# 3_LEDDRIVERS.net
KiCad netlist of a schematic drawn in Altium Designer
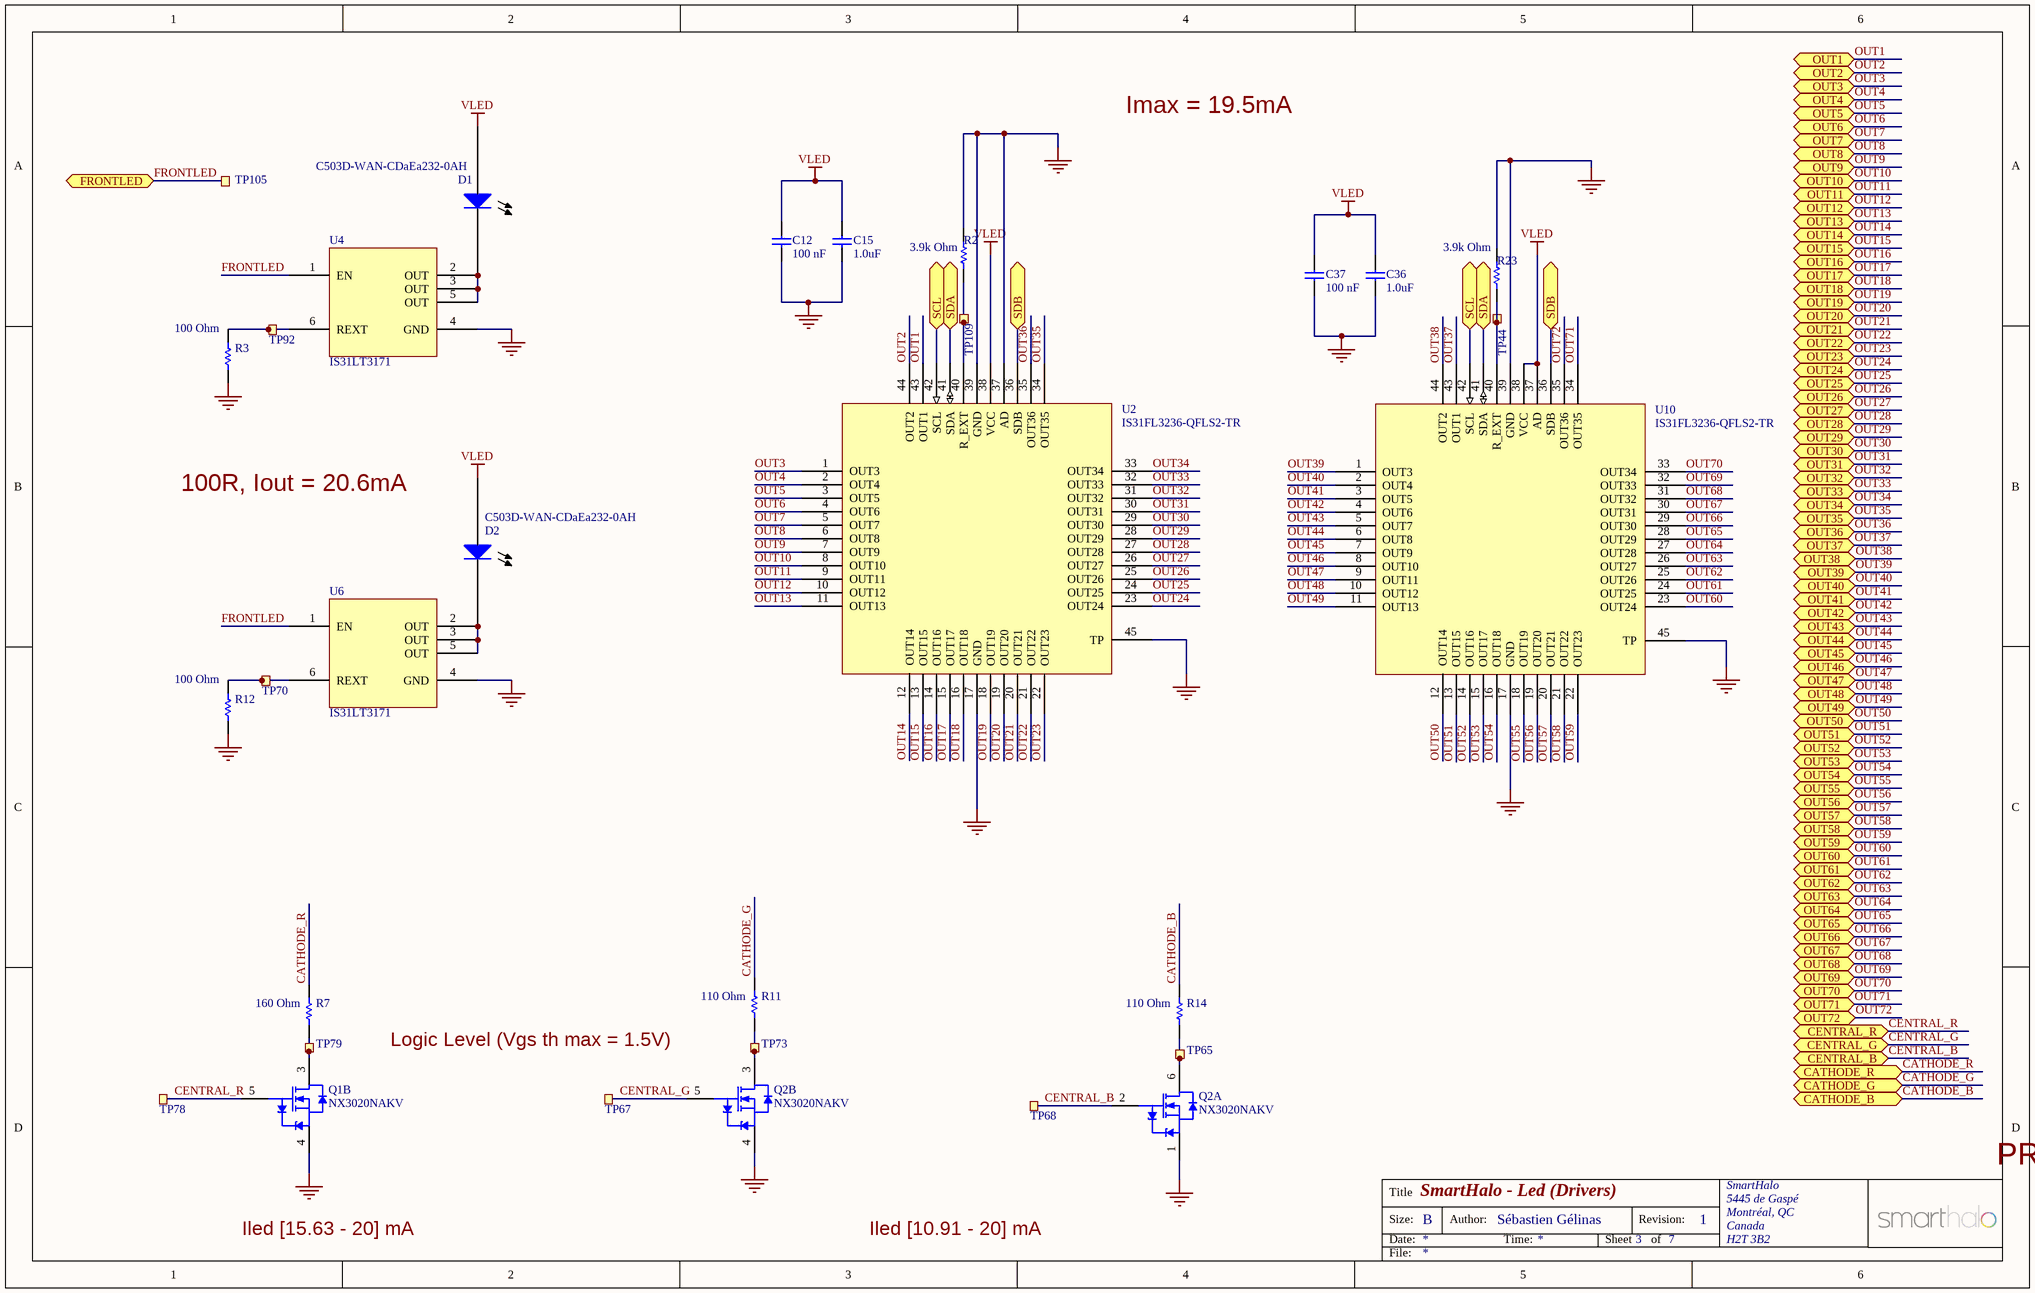
[diagram p0: 3_LEDDRIVERS.SchDoc]

(export (version "E")
  (design (tool "Eeschema 10.0.6"))
  (components
    (comp (ref "C12")
      (value "100 nF")
      (footprint "Varitron_CAP0402")
      (description "100 nF 10V X7R 10% 0402 (1005 Metric)  SMD")
      (fields (field (name "TOLERANCE") "10%"))
      (libsource (lib "SmartHalo") (part "Varitron_CAP0402"))
    )
    (comp (ref "C15")
      (value "1.0uF")
      (footprint "Varitron_CAP0603")
      (description "1uF 10V X7R 10% 0603 (1608 Metric)  SMD")
      (fields (field (name "TOLERANCE") "10%"))
      (libsource (lib "SmartHalo") (part "Varitron_CAP0603"))
    )
    (comp (ref "C36")
      (value "1.0uF")
      (footprint "Varitron_CAP0603")
      (description "1uF 10V X7R 10% 0603 (1608 Metric)  SMD")
      (fields (field (name "TOLERANCE") "10%"))
      (libsource (lib "SmartHalo") (part "Varitron_CAP0603"))
    )
    (comp (ref "C37")
      (value "100 nF")
      (footprint "Varitron_CAP0402")
      (description "100 nF 10V X7R 10% 0402 (1005 Metric)  SMD")
      (fields (field (name "TOLERANCE") "10%"))
      (libsource (lib "SmartHalo") (part "Varitron_CAP0402"))
    )
    (comp (ref "D1")
      (value "C503D-WAN-CDaEa232-0AH")
      (footprint "FRONTLED_PADS")
      (description "Cree 5mm Round LED C503D-WAN-CDaEa232-0AH")
      (fields (field (name "MANUFACTURER") "Cree"))
      (libsource (lib "SmartHalo") (part "C503D-WAN-CDaEa232-0AH"))
    )
    (comp (ref "D2")
      (value "C503D-WAN-CDaEa232-0AH")
      (footprint "FRONTLED_PADS")
      (description "Cree 5mm Round LED C503D-WAN-CDaEa232-0AH")
      (fields (field (name "MANUFACTURER") "Cree"))
      (libsource (lib "SmartHalo") (part "C503D-WAN-CDaEa232-0AH"))
    )
    (comp (ref "Q1")
      (value "NX3020NAKV")
      (footprint "SOT666")
      (description "30 V, 200 mA dual N-channel Trench MOSFET")
      (fields (field (name "MANUFACTURER") "NXP Semiconductors"))
      (libsource (lib "SmartHalo") (part "NX3020NAKV"))
    )
    (comp (ref "Q2")
      (value "NX3020NAKV")
      (footprint "SOT666")
      (description "30 V, 200 mA dual N-channel Trench MOSFET")
      (fields (field (name "MANUFACTURER") "NXP Semiconductors"))
      (libsource (lib "SmartHalo") (part "NX3020NAKV"))
    )
    (comp (ref "R2")
      (value "3.9k Ohm")
      (footprint "Varitron_RES0402")
      (description "3K9 0.063W 5%  0402 (1005 Metric)  SMD")
      (fields (field (name "TOLERANCE") "5%") (field (name "POWER") "0.063W"))
      (libsource (lib "SmartHalo") (part "Varitron_RES0402"))
    )
    (comp (ref "R3")
      (value "100 Ohm")
      (footprint "Varitron_RES0402")
      (description "100R 0.1W 5% 0402 (1005 Metric)  SMD")
      (fields (field (name "TOLERANCE") "5%") (field (name "POWER") "0.1W"))
      (libsource (lib "SmartHalo") (part "Varitron_RES0402"))
    )
    (comp (ref "R7")
      (value "160 Ohm")
      (footprint "Varitron_RES0402")
      (description "160R 0.1W 5% 0402 (1005 Metric)  SMD")
      (fields (field (name "TOLERANCE") "5%") (field (name "POWER") "0.1W"))
      (libsource (lib "SmartHalo") (part "Varitron_RES0402"))
    )
    (comp (ref "R11")
      (value "110 Ohm")
      (footprint "Varitron_RES0402")
      (description "110R 0.1W 5% 0402 (1005 Metric)  SMD")
      (fields (field (name "TOLERANCE") "5%") (field (name "POWER") "0.1W"))
      (libsource (lib "SmartHalo") (part "Varitron_RES0402"))
    )
    (comp (ref "R12")
      (value "100 Ohm")
      (footprint "Varitron_RES0402")
      (description "100R 0.1W 5% 0402 (1005 Metric)  SMD")
      (fields (field (name "TOLERANCE") "5%") (field (name "POWER") "0.1W"))
      (libsource (lib "SmartHalo") (part "Varitron_RES0402"))
    )
    (comp (ref "R14")
      (value "110 Ohm")
      (footprint "Varitron_RES0402")
      (description "110R 0.1W 5% 0402 (1005 Metric)  SMD")
      (fields (field (name "TOLERANCE") "5%") (field (name "POWER") "0.1W"))
      (libsource (lib "SmartHalo") (part "Varitron_RES0402"))
    )
    (comp (ref "R23")
      (value "3.9k Ohm")
      (footprint "Varitron_RES0402")
      (description "3K9 0.063W 5%  0402 (1005 Metric)  SMD")
      (fields (field (name "TOLERANCE") "5%") (field (name "POWER") "0.063W"))
      (libsource (lib "SmartHalo") (part "Varitron_RES0402"))
    )
    (comp (ref "TP44")
      (value "~")
      (footprint "TESTPAD-TH-35mils")
      (description "Testpoint, through hole, 35 mils")
      (libsource (lib "SmartHalo") (part "TESTPAD_TH_35mils"))
    )
    (comp (ref "TP65")
      (value "~")
      (footprint "TESTPAD-TH-35mils")
      (description "Testpoint, through hole, 35 mils")
      (libsource (lib "SmartHalo") (part "TESTPAD_TH_35mils"))
    )
    (comp (ref "TP67")
      (value "~")
      (footprint "TESTPAD-TH-35mils")
      (description "Testpoint, through hole, 35 mils")
      (libsource (lib "") (part "TESTPAD_TH_35mils_1"))
    )
    (comp (ref "TP68")
      (value "~")
      (footprint "TESTPAD-TH-35mils")
      (description "Testpoint, through hole, 35 mils")
      (libsource (lib "") (part "TESTPAD_TH_35mils_1"))
    )
    (comp (ref "TP70")
      (value "~")
      (footprint "TESTPAD-TH-35mils")
      (description "Testpoint, through hole, 35 mils")
      (libsource (lib "") (part "TESTPAD_TH_35mils_2"))
    )
    (comp (ref "TP73")
      (value "~")
      (footprint "TESTPAD-TH-35mils")
      (description "Testpoint, through hole, 35 mils")
      (libsource (lib "SmartHalo") (part "TESTPAD_TH_35mils"))
    )
    (comp (ref "TP78")
      (value "~")
      (footprint "TESTPAD-TH-35mils")
      (description "Testpoint, through hole, 35 mils")
      (libsource (lib "") (part "TESTPAD_TH_35mils_1"))
    )
    (comp (ref "TP79")
      (value "~")
      (footprint "TESTPAD-TH-35mils")
      (description "Testpoint, through hole, 35 mils")
      (libsource (lib "SmartHalo") (part "TESTPAD_TH_35mils"))
    )
    (comp (ref "TP92")
      (value "~")
      (footprint "TESTPAD-TH-35mils")
      (description "Testpoint, through hole, 35 mils")
      (libsource (lib "") (part "TESTPAD_TH_35mils_2"))
    )
    (comp (ref "TP105")
      (value "~")
      (footprint "TESTPAD-TH-35mils")
      (description "Testpoint, through hole, 35 mils")
      (libsource (lib "") (part "TESTPAD_TH_35mils_2"))
    )
    (comp (ref "TP109")
      (value "~")
      (footprint "TESTPAD-TH-35mils")
      (description "Testpoint, through hole, 35 mils")
      (libsource (lib "SmartHalo") (part "TESTPAD_TH_35mils"))
    )
    (comp (ref "U2")
      (value "IS31FL3236-QFLS2-TR")
      (footprint "QFN-44")
      (description "IC 36 CHANNELS LED DRIVER")
      (fields (field (name "MANUFACTURER") "ISSI"))
      (libsource (lib "SmartHalo_Symbols") (part "IS31FL3236-QFLS2-TR"))
    )
    (comp (ref "U4")
      (value "IS31LT3171")
      (footprint "SOT23-6")
      (description "10-TO-150MA CONSTANT-CURRENT LED DRIVER")
      (fields (field (name "MANUFACTURER") "ISSI"))
      (libsource (lib "SmartHalo") (part "IS31LT3171"))
    )
    (comp (ref "U6")
      (value "IS31LT3171")
      (footprint "SOT23-6")
      (description "10-TO-150MA CONSTANT-CURRENT LED DRIVER")
      (fields (field (name "MANUFACTURER") "ISSI"))
      (libsource (lib "SmartHalo") (part "IS31LT3171"))
    )
    (comp (ref "U10")
      (value "IS31FL3236-QFLS2-TR")
      (footprint "QFN-44")
      (description "IC 36 CHANNELS LED DRIVER")
      (fields (field (name "MANUFACTURER") "ISSI"))
      (libsource (lib "SmartHalo_Symbols") (part "IS31FL3236-QFLS2-TR"))
    )
  )
  (nets
    (net (code "1") (name "/CATHODE_B") (class "Default")
      (node (ref "R14") (pin "2") (pinfunction "2_2") (pintype "passive"))
    )
    (net (code "2") (name "/CATHODE_G") (class "Default")
      (node (ref "R11") (pin "2") (pinfunction "2_2") (pintype "passive"))
    )
    (net (code "3") (name "/CATHODE_R") (class "Default")
      (node (ref "R7") (pin "2") (pinfunction "2_2") (pintype "passive"))
    )
    (net (code "4") (name "/CENTRAL_B") (class "Default")
      (node (ref "Q2") (pin "2") (pinfunction "G1_2") (pintype "passive"))
      (node (ref "TP68") (pin "1") (pinfunction "1_1") (pintype "passive"))
    )
    (net (code "5") (name "/CENTRAL_G") (class "Default")
      (node (ref "Q2") (pin "5") (pinfunction "G2_5") (pintype "passive"))
      (node (ref "TP67") (pin "1") (pinfunction "1_1") (pintype "passive"))
    )
    (net (code "6") (name "/CENTRAL_R") (class "Default")
      (node (ref "Q1") (pin "5") (pinfunction "G2_5") (pintype "passive"))
      (node (ref "TP78") (pin "1") (pinfunction "1_1") (pintype "passive"))
    )
    (net (code "7") (name "/FRONTLED") (class "Default")
      (node (ref "TP105") (pin "1") (pinfunction "1_1") (pintype "passive"))
      (node (ref "U4") (pin "1") (pinfunction "EN_1") (pintype "passive"))
      (node (ref "U6") (pin "1") (pinfunction "EN_1") (pintype "passive"))
    )
    (net (code "8") (name "/OUT1") (class "Default")
      (node (ref "U2") (pin "43") (pinfunction "OUT1_43") (pintype "passive"))
    )
    (net (code "9") (name "/OUT2") (class "Default")
      (node (ref "U2") (pin "44") (pinfunction "OUT2_44") (pintype "passive"))
    )
    (net (code "10") (name "/OUT3") (class "Default")
      (node (ref "U2") (pin "1") (pinfunction "OUT3_1") (pintype "passive"))
    )
    (net (code "11") (name "/OUT4") (class "Default")
      (node (ref "U2") (pin "2") (pinfunction "OUT4_2") (pintype "passive"))
    )
    (net (code "12") (name "/OUT5") (class "Default")
      (node (ref "U2") (pin "3") (pinfunction "OUT5_3") (pintype "passive"))
    )
    (net (code "13") (name "/OUT6") (class "Default")
      (node (ref "U2") (pin "4") (pinfunction "OUT6_4") (pintype "passive"))
    )
    (net (code "14") (name "/OUT7") (class "Default")
      (node (ref "U2") (pin "5") (pinfunction "OUT7_5") (pintype "passive"))
    )
    (net (code "15") (name "/OUT8") (class "Default")
      (node (ref "U2") (pin "6") (pinfunction "OUT8_6") (pintype "passive"))
    )
    (net (code "16") (name "/OUT9") (class "Default")
      (node (ref "U2") (pin "7") (pinfunction "OUT9_7") (pintype "passive"))
    )
    (net (code "17") (name "/OUT10") (class "Default")
      (node (ref "U2") (pin "8") (pinfunction "OUT10_8") (pintype "passive"))
    )
    (net (code "18") (name "/OUT11") (class "Default")
      (node (ref "U2") (pin "9") (pinfunction "OUT11_9") (pintype "passive"))
    )
    (net (code "19") (name "/OUT12") (class "Default")
      (node (ref "U2") (pin "10") (pinfunction "OUT12_10") (pintype "passive"))
    )
    (net (code "20") (name "/OUT13") (class "Default")
      (node (ref "U2") (pin "11") (pinfunction "OUT13_11") (pintype "passive"))
    )
    (net (code "21") (name "/OUT14") (class "Default")
      (node (ref "U2") (pin "12") (pinfunction "OUT14_12") (pintype "passive"))
    )
    (net (code "22") (name "/OUT15") (class "Default")
      (node (ref "U2") (pin "13") (pinfunction "OUT15_13") (pintype "passive"))
    )
    (net (code "23") (name "/OUT16") (class "Default")
      (node (ref "U2") (pin "14") (pinfunction "OUT16_14") (pintype "passive"))
    )
    (net (code "24") (name "/OUT17") (class "Default")
      (node (ref "U2") (pin "15") (pinfunction "OUT17_15") (pintype "passive"))
    )
    (net (code "25") (name "/OUT18") (class "Default")
      (node (ref "U2") (pin "16") (pinfunction "OUT18_16") (pintype "passive"))
    )
    (net (code "26") (name "/OUT19") (class "Default")
      (node (ref "U2") (pin "18") (pinfunction "OUT19_18") (pintype "passive"))
    )
    (net (code "27") (name "/OUT20") (class "Default")
      (node (ref "U2") (pin "19") (pinfunction "OUT20_19") (pintype "passive"))
    )
    (net (code "28") (name "/OUT21") (class "Default")
      (node (ref "U2") (pin "20") (pinfunction "OUT21_20") (pintype "passive"))
    )
    (net (code "29") (name "/OUT22") (class "Default")
      (node (ref "U2") (pin "21") (pinfunction "OUT22_21") (pintype "passive"))
    )
    (net (code "30") (name "/OUT23") (class "Default")
      (node (ref "U2") (pin "22") (pinfunction "OUT23_22") (pintype "passive"))
    )
    (net (code "31") (name "/OUT24") (class "Default")
      (node (ref "U2") (pin "23") (pinfunction "OUT24_23") (pintype "passive"))
    )
    (net (code "32") (name "/OUT25") (class "Default")
      (node (ref "U2") (pin "24") (pinfunction "OUT25_24") (pintype "passive"))
    )
    (net (code "33") (name "/OUT26") (class "Default")
      (node (ref "U2") (pin "25") (pinfunction "OUT26_25") (pintype "passive"))
    )
    (net (code "34") (name "/OUT27") (class "Default")
      (node (ref "U2") (pin "26") (pinfunction "OUT27_26") (pintype "passive"))
    )
    (net (code "35") (name "/OUT28") (class "Default")
      (node (ref "U2") (pin "27") (pinfunction "OUT28_27") (pintype "passive"))
    )
    (net (code "36") (name "/OUT29") (class "Default")
      (node (ref "U2") (pin "28") (pinfunction "OUT29_28") (pintype "passive"))
    )
    (net (code "37") (name "/OUT30") (class "Default")
      (node (ref "U2") (pin "29") (pinfunction "OUT30_29") (pintype "passive"))
    )
    (net (code "38") (name "/OUT31") (class "Default")
      (node (ref "U2") (pin "30") (pinfunction "OUT31_30") (pintype "passive"))
    )
    (net (code "39") (name "/OUT32") (class "Default")
      (node (ref "U2") (pin "31") (pinfunction "OUT32_31") (pintype "passive"))
    )
    (net (code "40") (name "/OUT33") (class "Default")
      (node (ref "U2") (pin "32") (pinfunction "OUT33_32") (pintype "passive"))
    )
    (net (code "41") (name "/OUT34") (class "Default")
      (node (ref "U2") (pin "33") (pinfunction "OUT34_33") (pintype "passive"))
    )
    (net (code "42") (name "/OUT35") (class "Default")
      (node (ref "U2") (pin "34") (pinfunction "OUT35_34") (pintype "passive"))
    )
    (net (code "43") (name "/OUT36") (class "Default")
      (node (ref "U2") (pin "35") (pinfunction "OUT36_35") (pintype "passive"))
    )
    (net (code "44") (name "/OUT37") (class "Default")
      (node (ref "U10") (pin "43") (pinfunction "OUT1_43") (pintype "passive"))
    )
    (net (code "45") (name "/OUT38") (class "Default")
      (node (ref "U10") (pin "44") (pinfunction "OUT2_44") (pintype "passive"))
    )
    (net (code "46") (name "/OUT39") (class "Default")
      (node (ref "U10") (pin "1") (pinfunction "OUT3_1") (pintype "passive"))
    )
    (net (code "47") (name "/OUT40") (class "Default")
      (node (ref "U10") (pin "2") (pinfunction "OUT4_2") (pintype "passive"))
    )
    (net (code "48") (name "/OUT41") (class "Default")
      (node (ref "U10") (pin "3") (pinfunction "OUT5_3") (pintype "passive"))
    )
    (net (code "49") (name "/OUT42") (class "Default")
      (node (ref "U10") (pin "4") (pinfunction "OUT6_4") (pintype "passive"))
    )
    (net (code "50") (name "/OUT43") (class "Default")
      (node (ref "U10") (pin "5") (pinfunction "OUT7_5") (pintype "passive"))
    )
    (net (code "51") (name "/OUT44") (class "Default")
      (node (ref "U10") (pin "6") (pinfunction "OUT8_6") (pintype "passive"))
    )
    (net (code "52") (name "/OUT45") (class "Default")
      (node (ref "U10") (pin "7") (pinfunction "OUT9_7") (pintype "passive"))
    )
    (net (code "53") (name "/OUT46") (class "Default")
      (node (ref "U10") (pin "8") (pinfunction "OUT10_8") (pintype "passive"))
    )
    (net (code "54") (name "/OUT47") (class "Default")
      (node (ref "U10") (pin "9") (pinfunction "OUT11_9") (pintype "passive"))
    )
    (net (code "55") (name "/OUT48") (class "Default")
      (node (ref "U10") (pin "10") (pinfunction "OUT12_10") (pintype "passive"))
    )
    (net (code "56") (name "/OUT49") (class "Default")
      (node (ref "U10") (pin "11") (pinfunction "OUT13_11") (pintype "passive"))
    )
    (net (code "57") (name "/OUT50") (class "Default")
      (node (ref "U10") (pin "12") (pinfunction "OUT14_12") (pintype "passive"))
    )
    (net (code "58") (name "/OUT51") (class "Default")
      (node (ref "U10") (pin "13") (pinfunction "OUT15_13") (pintype "passive"))
    )
    (net (code "59") (name "/OUT52") (class "Default")
      (node (ref "U10") (pin "14") (pinfunction "OUT16_14") (pintype "passive"))
    )
    (net (code "60") (name "/OUT53") (class "Default")
      (node (ref "U10") (pin "15") (pinfunction "OUT17_15") (pintype "passive"))
    )
    (net (code "61") (name "/OUT54") (class "Default")
      (node (ref "U10") (pin "16") (pinfunction "OUT18_16") (pintype "passive"))
    )
    (net (code "62") (name "/OUT55") (class "Default")
      (node (ref "U10") (pin "18") (pinfunction "OUT19_18") (pintype "passive"))
    )
    (net (code "63") (name "/OUT56") (class "Default")
      (node (ref "U10") (pin "19") (pinfunction "OUT20_19") (pintype "passive"))
    )
    (net (code "64") (name "/OUT57") (class "Default")
      (node (ref "U10") (pin "20") (pinfunction "OUT21_20") (pintype "passive"))
    )
    (net (code "65") (name "/OUT58") (class "Default")
      (node (ref "U10") (pin "21") (pinfunction "OUT22_21") (pintype "passive"))
    )
    (net (code "66") (name "/OUT59") (class "Default")
      (node (ref "U10") (pin "22") (pinfunction "OUT23_22") (pintype "passive"))
    )
    (net (code "67") (name "/OUT60") (class "Default")
      (node (ref "U10") (pin "23") (pinfunction "OUT24_23") (pintype "passive"))
    )
    (net (code "68") (name "/OUT61") (class "Default")
      (node (ref "U10") (pin "24") (pinfunction "OUT25_24") (pintype "passive"))
    )
    (net (code "69") (name "/OUT62") (class "Default")
      (node (ref "U10") (pin "25") (pinfunction "OUT26_25") (pintype "passive"))
    )
    (net (code "70") (name "/OUT63") (class "Default")
      (node (ref "U10") (pin "26") (pinfunction "OUT27_26") (pintype "passive"))
    )
    (net (code "71") (name "/OUT64") (class "Default")
      (node (ref "U10") (pin "27") (pinfunction "OUT28_27") (pintype "passive"))
    )
    (net (code "72") (name "/OUT65") (class "Default")
      (node (ref "U10") (pin "28") (pinfunction "OUT29_28") (pintype "passive"))
    )
    (net (code "73") (name "/OUT66") (class "Default")
      (node (ref "U10") (pin "29") (pinfunction "OUT30_29") (pintype "passive"))
    )
    (net (code "74") (name "/OUT67") (class "Default")
      (node (ref "U10") (pin "30") (pinfunction "OUT31_30") (pintype "passive"))
    )
    (net (code "75") (name "/OUT68") (class "Default")
      (node (ref "U10") (pin "31") (pinfunction "OUT32_31") (pintype "passive"))
    )
    (net (code "76") (name "/OUT69") (class "Default")
      (node (ref "U10") (pin "32") (pinfunction "OUT33_32") (pintype "passive"))
    )
    (net (code "77") (name "/OUT70") (class "Default")
      (node (ref "U10") (pin "33") (pinfunction "OUT34_33") (pintype "passive"))
    )
    (net (code "78") (name "/OUT71") (class "Default")
      (node (ref "U10") (pin "34") (pinfunction "OUT35_34") (pintype "passive"))
    )
    (net (code "79") (name "/OUT72") (class "Default")
      (node (ref "U10") (pin "35") (pinfunction "OUT36_35") (pintype "passive"))
    )
    (net (code "80") (name "/SCL") (class "Default")
      (node (ref "U10") (pin "42") (pinfunction "SCL_42") (pintype "input"))
      (node (ref "U2") (pin "42") (pinfunction "SCL_42") (pintype "input"))
    )
    (net (code "81") (name "/SDA") (class "Default")
      (node (ref "U10") (pin "41") (pinfunction "SDA_41") (pintype "bidirectional"))
      (node (ref "U2") (pin "41") (pinfunction "SDA_41") (pintype "bidirectional"))
    )
    (net (code "82") (name "/SDB") (class "Default")
      (node (ref "U10") (pin "36") (pinfunction "SDB_36") (pintype "passive"))
      (node (ref "U2") (pin "36") (pinfunction "SDB_36") (pintype "passive"))
    )
    (net (code "83") (name "GND") (class "Default")
      (node (ref "C12") (pin "2") (pinfunction "2_2") (pintype "passive"))
      (node (ref "C15") (pin "2") (pinfunction "2_2") (pintype "passive"))
      (node (ref "C36") (pin "2") (pinfunction "2_2") (pintype "passive"))
      (node (ref "C37") (pin "2") (pinfunction "2_2") (pintype "passive"))
      (node (ref "Q1") (pin "4") (pinfunction "S2_4") (pintype "passive"))
      (node (ref "Q2") (pin "1") (pinfunction "S1_1") (pintype "passive"))
      (node (ref "Q2") (pin "4") (pinfunction "S2_4") (pintype "passive"))
      (node (ref "R12") (pin "1") (pinfunction "1_1") (pintype "passive"))
      (node (ref "R2") (pin "2") (pinfunction "2_2") (pintype "passive"))
      (node (ref "R23") (pin "2") (pinfunction "2_2") (pintype "passive"))
      (node (ref "R3") (pin "1") (pinfunction "1_1") (pintype "passive"))
      (node (ref "U10") (pin "17") (pinfunction "GND_17") (pintype "power_in"))
      (node (ref "U10") (pin "39") (pinfunction "GND_39") (pintype "power_in"))
      (node (ref "U10") (pin "45") (pinfunction "TP_45") (pintype "power_in"))
      (node (ref "U2") (pin "17") (pinfunction "GND_17") (pintype "power_in"))
      (node (ref "U2") (pin "37") (pinfunction "AD_37") (pintype "passive"))
      (node (ref "U2") (pin "39") (pinfunction "GND_39") (pintype "power_in"))
      (node (ref "U2") (pin "45") (pinfunction "TP_45") (pintype "power_in"))
      (node (ref "U4") (pin "4") (pinfunction "GND_4") (pintype "passive"))
      (node (ref "U6") (pin "4") (pinfunction "GND_4") (pintype "passive"))
    )
    (net (code "84") (name "Net-(D1-Cathode)") (class "Default")
      (node (ref "D1") (pin "2") (pinfunction "Cathode_2") (pintype "passive"))
      (node (ref "U4") (pin "2") (pinfunction "OUT_2") (pintype "passive"))
      (node (ref "U4") (pin "3") (pinfunction "OUT_3") (pintype "passive"))
      (node (ref "U4") (pin "5") (pinfunction "OUT_5") (pintype "passive"))
    )
    (net (code "85") (name "Net-(D2-Cathode)") (class "Default")
      (node (ref "D2") (pin "2") (pinfunction "Cathode_2") (pintype "passive"))
      (node (ref "U6") (pin "2") (pinfunction "OUT_2") (pintype "passive"))
      (node (ref "U6") (pin "3") (pinfunction "OUT_3") (pintype "passive"))
      (node (ref "U6") (pin "5") (pinfunction "OUT_5") (pintype "passive"))
    )
    (net (code "86") (name "Net-(Q1B-D2)") (class "Default")
      (node (ref "Q1") (pin "3") (pinfunction "D2_3") (pintype "passive"))
      (node (ref "R7") (pin "1") (pinfunction "1_1") (pintype "passive"))
      (node (ref "TP79") (pin "1") (pinfunction "1_1") (pintype "passive"))
    )
    (net (code "87") (name "Net-(Q2A-D1)") (class "Default")
      (node (ref "Q2") (pin "6") (pinfunction "D1_6") (pintype "passive"))
      (node (ref "R14") (pin "1") (pinfunction "1_1") (pintype "passive"))
      (node (ref "TP65") (pin "1") (pinfunction "1_1") (pintype "passive"))
    )
    (net (code "88") (name "Net-(Q2B-D2)") (class "Default")
      (node (ref "Q2") (pin "3") (pinfunction "D2_3") (pintype "passive"))
      (node (ref "R11") (pin "1") (pinfunction "1_1") (pintype "passive"))
      (node (ref "TP73") (pin "1") (pinfunction "1_1") (pintype "passive"))
    )
    (net (code "89") (name "Net-(U2-R_EXT)") (class "Default")
      (node (ref "R2") (pin "1") (pinfunction "1_1") (pintype "passive"))
      (node (ref "TP109") (pin "1") (pinfunction "1_1") (pintype "passive"))
      (node (ref "U2") (pin "40") (pinfunction "R_EXT_40") (pintype "passive"))
    )
    (net (code "90") (name "Net-(U4-REXT)") (class "Default")
      (node (ref "R3") (pin "2") (pinfunction "2_2") (pintype "passive"))
      (node (ref "TP92") (pin "1") (pinfunction "1_1") (pintype "passive"))
      (node (ref "U4") (pin "6") (pinfunction "REXT_6") (pintype "passive"))
    )
    (net (code "91") (name "Net-(U6-REXT)") (class "Default")
      (node (ref "R12") (pin "2") (pinfunction "2_2") (pintype "passive"))
      (node (ref "TP70") (pin "1") (pinfunction "1_1") (pintype "passive"))
      (node (ref "U6") (pin "6") (pinfunction "REXT_6") (pintype "passive"))
    )
    (net (code "92") (name "Net-(U10-R_EXT)") (class "Default")
      (node (ref "R23") (pin "1") (pinfunction "1_1") (pintype "passive"))
      (node (ref "TP44") (pin "1") (pinfunction "1_1") (pintype "passive"))
      (node (ref "U10") (pin "40") (pinfunction "R_EXT_40") (pintype "passive"))
    )
    (net (code "93") (name "VLED") (class "Default")
      (node (ref "C12") (pin "1") (pinfunction "1_1") (pintype "passive"))
      (node (ref "C15") (pin "1") (pinfunction "1_1") (pintype "passive"))
      (node (ref "C36") (pin "1") (pinfunction "1_1") (pintype "passive"))
      (node (ref "C37") (pin "1") (pinfunction "1_1") (pintype "passive"))
      (node (ref "D1") (pin "1") (pinfunction "Anode_1") (pintype "passive"))
      (node (ref "D2") (pin "1") (pinfunction "Anode_1") (pintype "passive"))
      (node (ref "U10") (pin "37") (pinfunction "AD_37") (pintype "passive"))
      (node (ref "U10") (pin "38") (pinfunction "VCC_38") (pintype "power_in"))
      (node (ref "U2") (pin "38") (pinfunction "VCC_38") (pintype "power_in"))
    )
  )
)
